# TSOC_GROVEY_FOUR.net
KiCad netlist of a schematic drawn in EAGLE
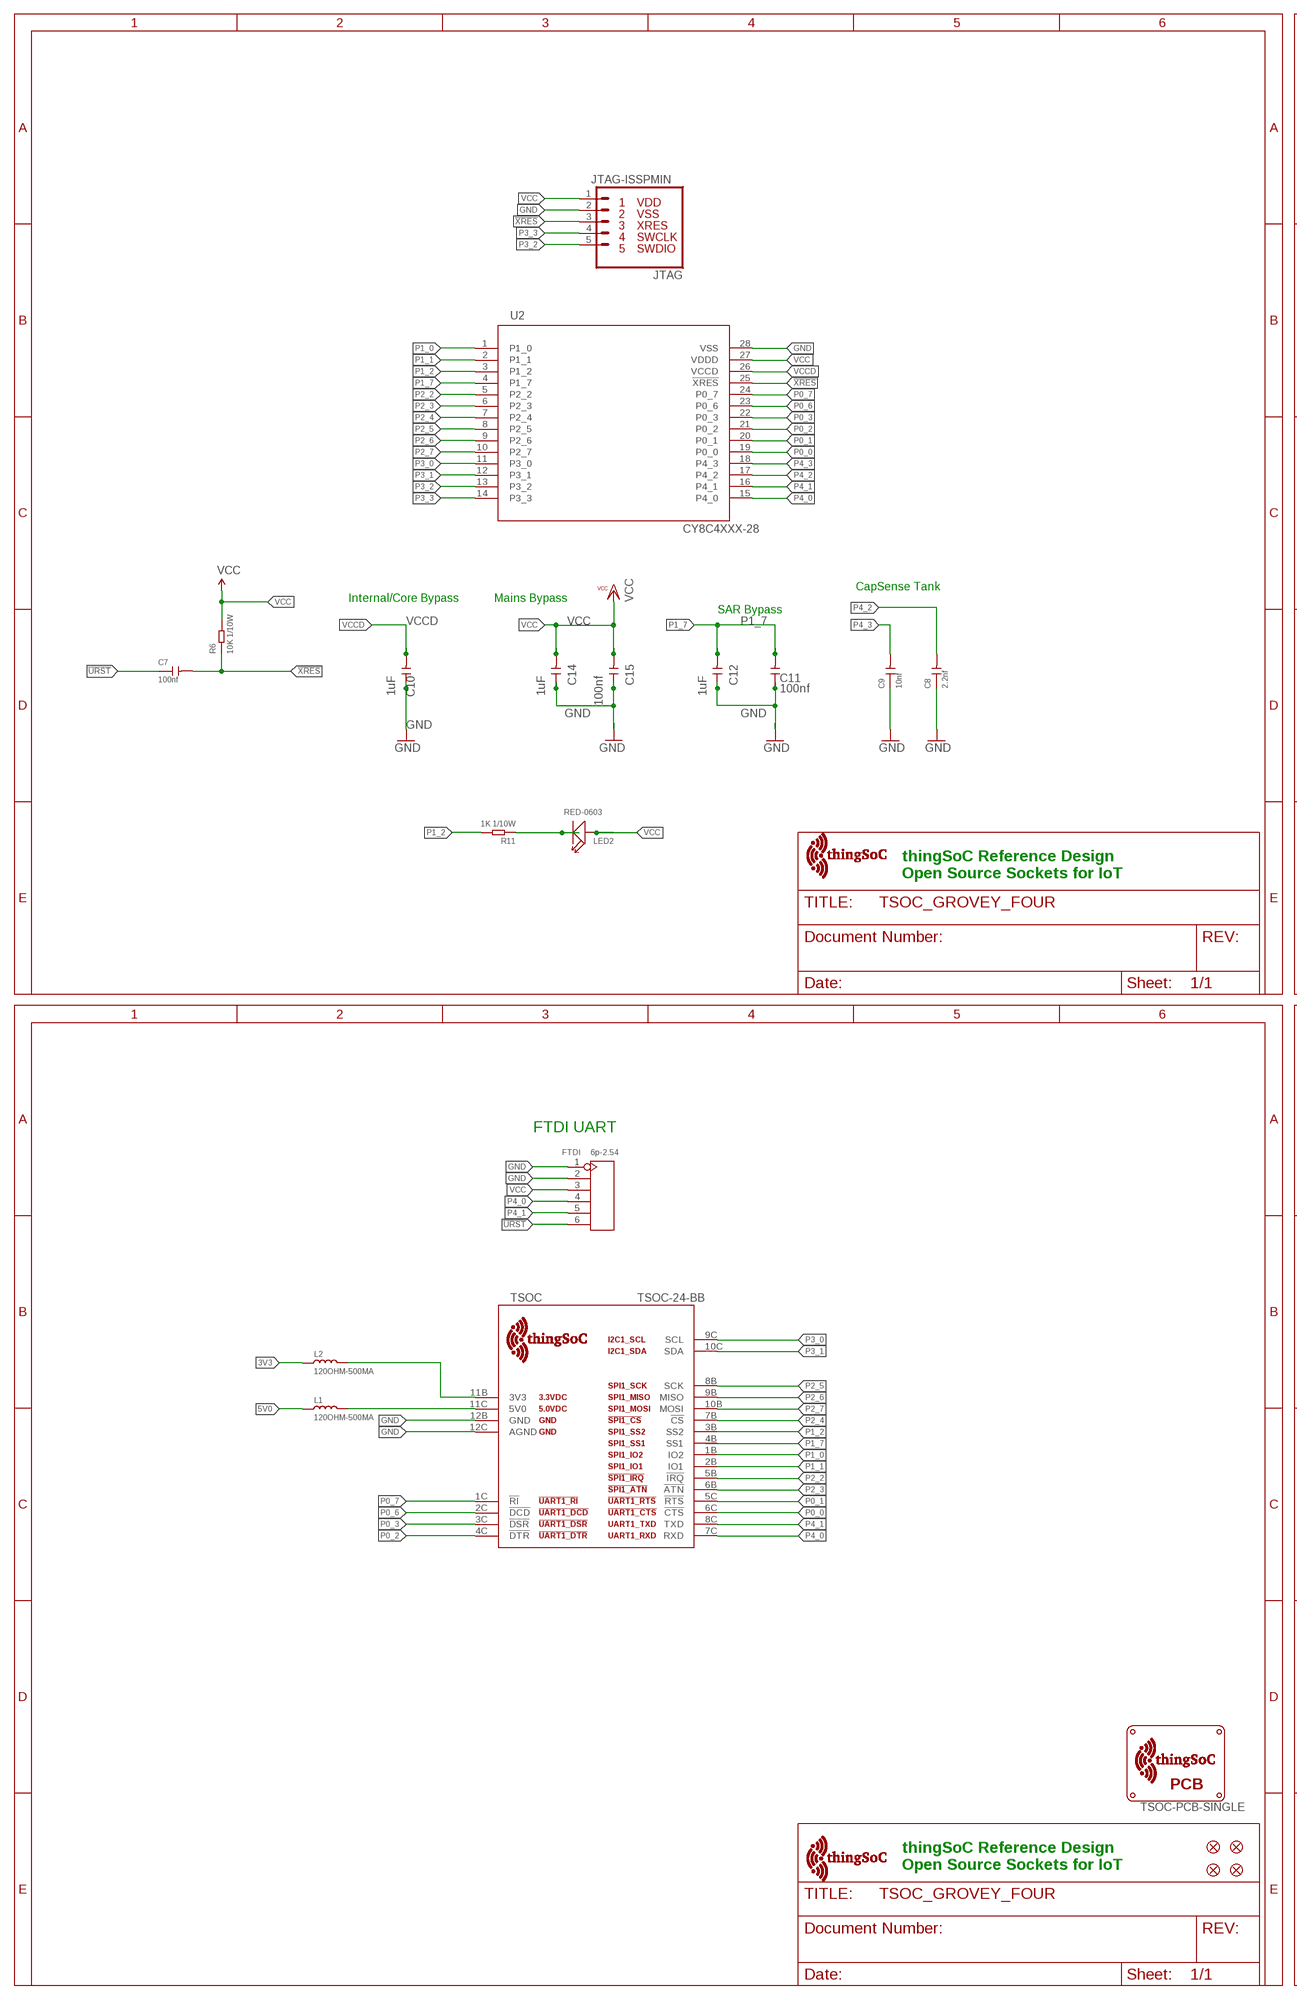
[diagram p0: schematic, sheet 1, part 1 of 2]
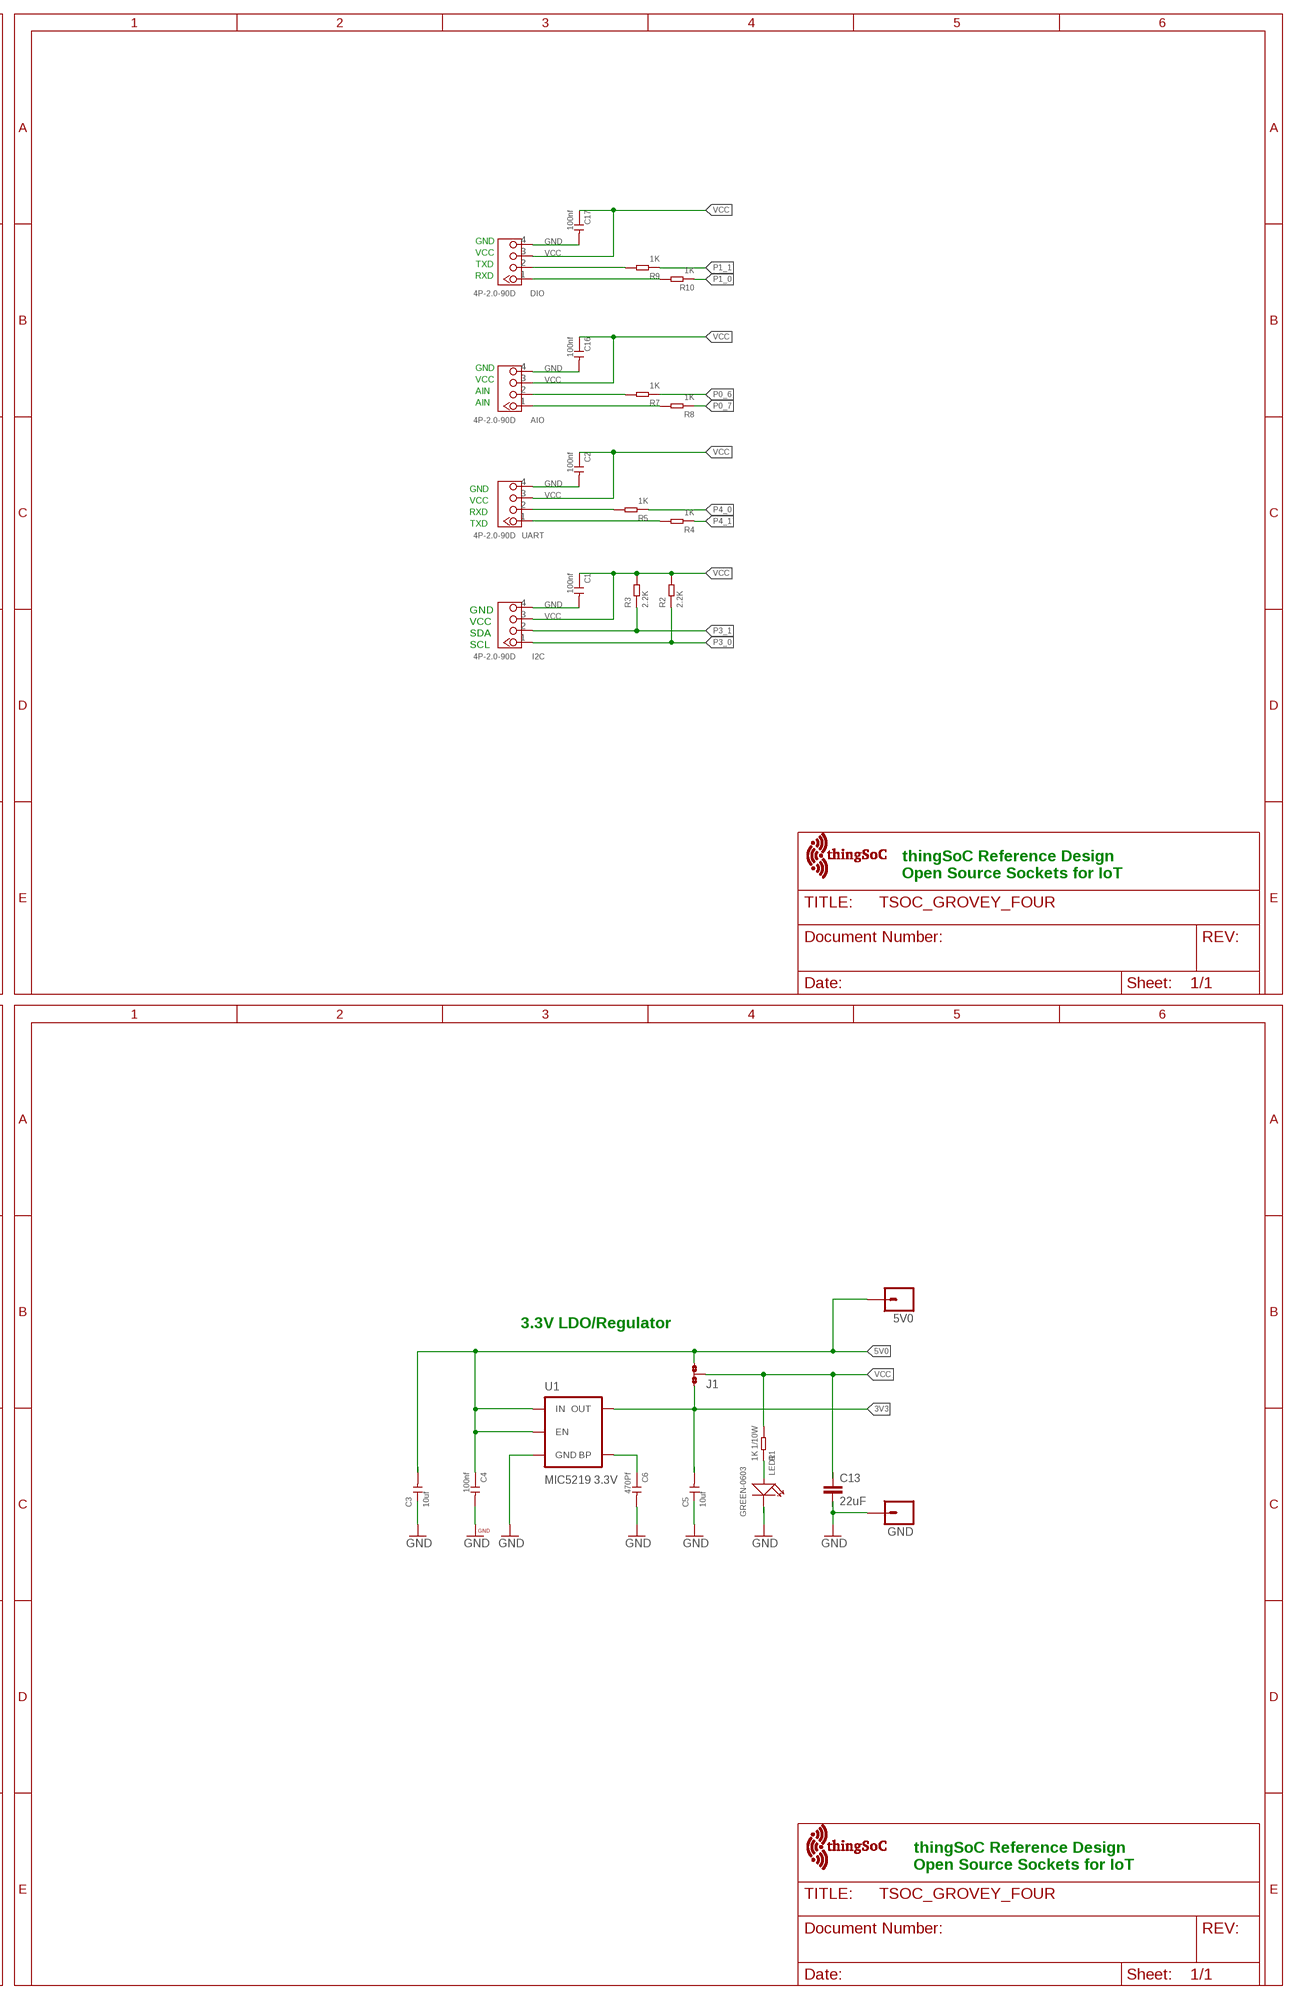
[diagram p1: schematic, sheet 1, part 2 of 2]

(export (version "E")
  (design (tool "Eeschema 10.0.6"))
  (components
    (comp (ref "$$U$1")
      (value "TSOC-PCB-SINGLE")
      (footprint "eagle-import:TSOC-BB-BRD-DIM")
      (libsource (lib "eagle-import") (part "TSOC-PCB-SINGLE"))
    )
    (comp (ref "5V0")
      (value "M01PTH")
      (footprint "eagle-import:1X01")
      (libsource (lib "eagle-import") (part "M01PTH"))
    )
    (comp (ref "AIO")
      (value "4P-2.0-90D")
      (footprint "eagle-import:HW4-2.0-90D")
      (libsource (lib "eagle-import") (part "GROVE-CONNECTOR-DIP-90D(4P-2.0)"))
    )
    (comp (ref "C1")
      (value "100nf")
      (footprint "eagle-import:C0603")
      (fields (field (name "MPN") "CC0603KRX7R9BB104"))
      (libsource (lib "eagle-import") (part "CERAMIC-100NF-50V-10%-X7R(0603)"))
    )
    (comp (ref "C2")
      (value "100nf")
      (footprint "eagle-import:C0603")
      (fields (field (name "MPN") "CC0603KRX7R9BB104"))
      (libsource (lib "eagle-import") (part "CERAMIC-100NF-50V-10%-X7R(0603)"))
    )
    (comp (ref "C3")
      (value "10uf")
      (footprint "eagle-import:C0603")
      (fields (field (name "MPN") "CC0603KRX5R6BB106"))
      (libsource (lib "eagle-import") (part "CERAMIC-10UF-10V-10%-X5R(0603)"))
    )
    (comp (ref "C4")
      (value "100nf")
      (footprint "eagle-import:C0603")
      (fields (field (name "MPN") "CC0603KRX7R9BB104"))
      (libsource (lib "eagle-import") (part "CERAMIC-100NF-50V-10%-X7R(0603)"))
    )
    (comp (ref "C5")
      (value "10uf")
      (footprint "eagle-import:C0603")
      (fields (field (name "MPN") "CC0603KRX5R6BB106"))
      (libsource (lib "eagle-import") (part "CERAMIC-10UF-10V-10%-X5R(0603)"))
    )
    (comp (ref "C6")
      (value "470Pf")
      (footprint "eagle-import:C0603")
      (fields (field (name "MPN") "CC0603KRX7R9BB104"))
      (libsource (lib "eagle-import") (part "CERAMIC-100NF-50V-10%-X7R(0603)"))
    )
    (comp (ref "C7")
      (value "100nf")
      (footprint "eagle-import:C0603")
      (fields (field (name "MPN") "CC0603KRX7R9BB104"))
      (libsource (lib "eagle-import") (part "CERAMIC-100NF-50V-10%-X7R(0603)"))
    )
    (comp (ref "C8")
      (value "2.2nf")
      (footprint "eagle-import:C0603")
      (fields (field (name "MPN") "GRM1885C1H102JA01D"))
      (libsource (lib "eagle-import") (part "CERAMIC-1NF-50V-5%-C0G(0603)"))
    )
    (comp (ref "C9")
      (value "10nf")
      (footprint "eagle-import:C0603")
      (fields (field (name "MPN") "CC0603KRX7R9BB103"))
      (libsource (lib "eagle-import") (part "CERAMIC-10NF-50V-10%-X7R(0603)"))
    )
    (comp (ref "C10")
      (value "1uF")
      (footprint "eagle-import:C0603")
      (fields (field (name "MPN") "CC0603KRX7R9BB104"))
      (libsource (lib "eagle-import") (part "CERAMIC-100NF-50V-10%-X7R(0603)"))
    )
    (comp (ref "C11")
      (value "100nf")
      (footprint "eagle-import:C0603")
      (fields (field (name "MPN") "CC0603KRX7R9BB104"))
      (libsource (lib "eagle-import") (part "CERAMIC-100NF-50V-10%-X7R(0603)"))
    )
    (comp (ref "C12")
      (value "1uF")
      (footprint "eagle-import:C0603")
      (fields (field (name "MPN") "CC0603KRX7R9BB104"))
      (libsource (lib "eagle-import") (part "CERAMIC-100NF-50V-10%-X7R(0603)"))
    )
    (comp (ref "C13")
      (value "22uF")
      (footprint "eagle-import:EIA-1206")
      (libsource (lib "eagle-import") (part "CAP-1206"))
    )
    (comp (ref "C14")
      (value "1uF")
      (footprint "eagle-import:C0603")
      (fields (field (name "MPN") "CC0603KRX7R9BB104"))
      (libsource (lib "eagle-import") (part "CERAMIC-100NF-50V-10%-X7R(0603)"))
    )
    (comp (ref "C15")
      (value "100nf")
      (footprint "eagle-import:C0603")
      (fields (field (name "MPN") "CC0603KRX7R9BB104"))
      (libsource (lib "eagle-import") (part "CERAMIC-100NF-50V-10%-X7R(0603)"))
    )
    (comp (ref "C16")
      (value "100nf")
      (footprint "eagle-import:C0603")
      (fields (field (name "MPN") "CC0603KRX7R9BB104"))
      (libsource (lib "eagle-import") (part "CERAMIC-100NF-50V-10%-X7R(0603)"))
    )
    (comp (ref "C17")
      (value "100nf")
      (footprint "eagle-import:C0603")
      (fields (field (name "MPN") "CC0603KRX7R9BB104"))
      (libsource (lib "eagle-import") (part "CERAMIC-100NF-50V-10%-X7R(0603)"))
    )
    (comp (ref "DIO")
      (value "4P-2.0-90D")
      (footprint "eagle-import:HW4-2.0-90D")
      (libsource (lib "eagle-import") (part "GROVE-CONNECTOR-DIP-90D(4P-2.0)"))
    )
    (comp (ref "FID1")
      (value "FIDUCIALUFIDUCIAL")
      (footprint "eagle-import:MICRO-FIDUCIAL")
      (libsource (lib "eagle-import") (part "FIDUCIALUFIDUCIAL"))
    )
    (comp (ref "FID2")
      (value "FIDUCIALUFIDUCIAL")
      (footprint "eagle-import:MICRO-FIDUCIAL")
      (libsource (lib "eagle-import") (part "FIDUCIALUFIDUCIAL"))
    )
    (comp (ref "FID3")
      (value "FIDUCIALUFIDUCIAL")
      (footprint "eagle-import:MICRO-FIDUCIAL")
      (libsource (lib "eagle-import") (part "FIDUCIALUFIDUCIAL"))
    )
    (comp (ref "FID4")
      (value "FIDUCIALUFIDUCIAL")
      (footprint "eagle-import:MICRO-FIDUCIAL")
      (libsource (lib "eagle-import") (part "FIDUCIALUFIDUCIAL"))
    )
    (comp (ref "FTDI")
      (value "6p-2.54")
      (footprint "eagle-import:H6-2.54")
      (fields (field (name "MPN") "P125-1106A1BS116A1"))
      (libsource (lib "eagle-import") (part "DIP-BLACK-MALE-HEADER(6P-2.54)"))
    )
    (comp (ref "GND")
      (value "M01PTH")
      (footprint "eagle-import:1X01")
      (libsource (lib "eagle-import") (part "M01PTH"))
    )
    (comp (ref "I2C")
      (value "4P-2.0-90D")
      (footprint "eagle-import:HW4-2.0-90D")
      (libsource (lib "eagle-import") (part "GROVE-CONNECTOR-DIP-90D(4P-2.0)"))
    )
    (comp (ref "J1")
      (value "NO")
      (footprint "eagle-import:JMP-3-NO-PTH-2.54")
      (libsource (lib "eagle-import") (part "JMP-3-NO-PTH"))
    )
    (comp (ref "JTAG")
      (value "JTAG-ISSPMIN")
      (footprint "eagle-import:PSOC_JTAG_MINSILK")
      (libsource (lib "eagle-import") (part "JTAG-ISSPMIN"))
    )
    (comp (ref "L1")
      (value "120OHM-500MA")
      (footprint "eagle-import:L0603")
      (fields (field (name "MPN") "BLM18AG121SN1D"))
      (libsource (lib "eagle-import") (part "SMD-FERRITE-CHIP-120-OHM-500MA(0603)"))
    )
    (comp (ref "L2")
      (value "120OHM-500MA")
      (footprint "eagle-import:L0603")
      (fields (field (name "MPN") "BLM18AG121SN1D"))
      (libsource (lib "eagle-import") (part "SMD-FERRITE-CHIP-120-OHM-500MA(0603)"))
    )
    (comp (ref "LED1")
      (value "GREEN-0603")
      (footprint "eagle-import:LED-0603")
      (fields (field (name "MPN") "19-217-G7C-AN1P2-3T"))
      (libsource (lib "eagle-import") (part "SMD-LED-CLEAR-GREEN(0603)"))
    )
    (comp (ref "LED2")
      (value "RED-0603")
      (footprint "eagle-import:LED-0603")
      (fields (field (name "MPN") "19-217-G7C-AN1P2-3T"))
      (libsource (lib "eagle-import") (part "SMD-LED-CLEAR-GREEN(0603)"))
    )
    (comp (ref "R1")
      (value "1K 1/10W")
      (footprint "eagle-import:R0603")
      (fields (field (name "MPN") "RC0603JR-071KL"))
      (libsource (lib "eagle-import") (part "SMD-RES-1K-5%-1/10W(0603)"))
    )
    (comp (ref "R2")
      (value "2.2K")
      (footprint "eagle-import:R0603")
      (fields (field (name "MPN") "RC0603JR-072K2L"))
      (libsource (lib "eagle-import") (part "SMD-RES-2.2K-5%-1/10W(0603)"))
    )
    (comp (ref "R3")
      (value "2.2K")
      (footprint "eagle-import:R0603")
      (fields (field (name "MPN") "RC0603JR-072K2L"))
      (libsource (lib "eagle-import") (part "SMD-RES-2.2K-5%-1/10W(0603)"))
    )
    (comp (ref "R4")
      (value "1K")
      (footprint "eagle-import:R0603")
      (fields (field (name "MPN") "RC0603JR-072K2L"))
      (libsource (lib "eagle-import") (part "SMD-RES-2.2K-5%-1/10W(0603)"))
    )
    (comp (ref "R5")
      (value "1K")
      (footprint "eagle-import:R0603")
      (fields (field (name "MPN") "RC0603JR-072K2L"))
      (libsource (lib "eagle-import") (part "SMD-RES-2.2K-5%-1/10W(0603)"))
    )
    (comp (ref "R6")
      (value "10K 1/10W")
      (footprint "eagle-import:R0603")
      (fields (field (name "MPN") "RC0603JR-0710KL"))
      (libsource (lib "eagle-import") (part "SMD-RES-10K-5%-1/10W(0603)"))
    )
    (comp (ref "R7")
      (value "1K")
      (footprint "eagle-import:R0603")
      (fields (field (name "MPN") "RC0603JR-072K2L"))
      (libsource (lib "eagle-import") (part "SMD-RES-2.2K-5%-1/10W(0603)"))
    )
    (comp (ref "R8")
      (value "1K")
      (footprint "eagle-import:R0603")
      (fields (field (name "MPN") "RC0603JR-072K2L"))
      (libsource (lib "eagle-import") (part "SMD-RES-2.2K-5%-1/10W(0603)"))
    )
    (comp (ref "R9")
      (value "1K")
      (footprint "eagle-import:R0603")
      (fields (field (name "MPN") "RC0603JR-072K2L"))
      (libsource (lib "eagle-import") (part "SMD-RES-2.2K-5%-1/10W(0603)"))
    )
    (comp (ref "R10")
      (value "1K")
      (footprint "eagle-import:R0603")
      (fields (field (name "MPN") "RC0603JR-072K2L"))
      (libsource (lib "eagle-import") (part "SMD-RES-2.2K-5%-1/10W(0603)"))
    )
    (comp (ref "R11")
      (value "1K 1/10W")
      (footprint "eagle-import:R0603")
      (fields (field (name "MPN") "RC0603JR-071KL"))
      (libsource (lib "eagle-import") (part "SMD-RES-1K-5%-1/10W(0603)"))
    )
    (comp (ref "TSOC")
      (value "TSOC-24-BB")
      (footprint "eagle-import:TSOC-BB-S24")
      (libsource (lib "eagle-import") (part "TSOC-24-BB"))
    )
    (comp (ref "U$1")
      (value "TSOC-LOGO-SMALL")
      (footprint "eagle-import:TSOC-LOGO-SML")
      (libsource (lib "eagle-import") (part "TSOC-LOGO-SMALL"))
    )
    (comp (ref "U$4")
      (value "TSOC-LOGO")
      (footprint "eagle-import:TSOC-LOGO-BLANK")
      (libsource (lib "eagle-import") (part "TSOC-LOGO"))
    )
    (comp (ref "U$102")
      (value "TSOC-LOGO-LRG")
      (footprint "eagle-import:TSOC-LOGO-LRG")
      (libsource (lib "eagle-import") (part "TSOC-LOGO-LRG"))
    )
    (comp (ref "U$103")
      (value "TSOC-LOGO-SMALL")
      (footprint "eagle-import:TSOC-LOGO-SML")
      (libsource (lib "eagle-import") (part "TSOC-LOGO-SMALL"))
    )
    (comp (ref "U1")
      (value "MIC5219 3.3V")
      (footprint "eagle-import:SOT23-5")
      (libsource (lib "eagle-import") (part "V_REG_MIC52193.3V"))
    )
    (comp (ref "U2")
      (value "CY8C4XXX-28")
      (footprint "eagle-import:SSOP28")
      (libsource (lib "eagle-import") (part "CY8C4XXX-28"))
    )
    (comp (ref "UART")
      (value "4P-2.0-90D")
      (footprint "eagle-import:HW4-2.0-90D")
      (libsource (lib "eagle-import") (part "GROVE-CONNECTOR-DIP-90D(4P-2.0)"))
    )
  )
  (nets
    (net (code "1") (name "/~{URST}") (class "Default")
      (node (ref "C7") (pin "1") (pinfunction "1_1") (pintype "passive"))
      (node (ref "FTDI") (pin "6") (pinfunction "6_6") (pintype "bidirectional"))
    )
    (net (code "2") (name "/~{XRES}") (class "Default")
      (node (ref "C7") (pin "2") (pinfunction "2_2") (pintype "passive"))
      (node (ref "JTAG") (pin "3") (pinfunction "3_3") (pintype "passive"))
      (node (ref "R6") (pin "1") (pinfunction "1_1") (pintype "passive"))
      (node (ref "U2") (pin "25") (pinfunction "~{XRES}_25") (pintype "bidirectional"))
    )
    (net (code "3") (name "3V3") (class "Default")
      (node (ref "C5") (pin "2") (pinfunction "2_2") (pintype "passive"))
      (node (ref "J1") (pin "1") (pinfunction "1_1") (pintype "passive"))
      (node (ref "L2") (pin "1") (pinfunction "1_1") (pintype "passive"))
      (node (ref "U1") (pin "5") (pinfunction "OUT_5") (pintype "passive"))
    )
    (net (code "4") (name "5V0") (class "Default")
      (node (ref "5V0") (pin "1") (pinfunction "1_1") (pintype "passive"))
      (node (ref "C3") (pin "2") (pinfunction "2_2") (pintype "passive"))
      (node (ref "C4") (pin "1") (pinfunction "1_1") (pintype "passive"))
      (node (ref "J1") (pin "3") (pinfunction "3_3") (pintype "passive"))
      (node (ref "L1") (pin "1") (pinfunction "1_1") (pintype "passive"))
      (node (ref "U1") (pin "1") (pinfunction "IN_1") (pintype "input"))
      (node (ref "U1") (pin "3") (pinfunction "EN_3") (pintype "input"))
    )
    (net (code "5") (name "GND") (class "Default")
      (node (ref "AIO") (pin "4") (pinfunction "4_4") (pintype "bidirectional"))
      (node (ref "C1") (pin "2") (pinfunction "2_2") (pintype "passive"))
      (node (ref "C10") (pin "1") (pinfunction "1_1") (pintype "passive"))
      (node (ref "C11") (pin "1") (pinfunction "1_1") (pintype "passive"))
      (node (ref "C12") (pin "1") (pinfunction "1_1") (pintype "passive"))
      (node (ref "C13") (pin "2") (pinfunction "2_2") (pintype "passive"))
      (node (ref "C14") (pin "1") (pinfunction "1_1") (pintype "passive"))
      (node (ref "C15") (pin "1") (pinfunction "1_1") (pintype "passive"))
      (node (ref "C16") (pin "2") (pinfunction "2_2") (pintype "passive"))
      (node (ref "C17") (pin "2") (pinfunction "2_2") (pintype "passive"))
      (node (ref "C2") (pin "2") (pinfunction "2_2") (pintype "passive"))
      (node (ref "C3") (pin "1") (pinfunction "1_1") (pintype "passive"))
      (node (ref "C4") (pin "2") (pinfunction "2_2") (pintype "passive"))
      (node (ref "C5") (pin "1") (pinfunction "1_1") (pintype "passive"))
      (node (ref "C6") (pin "2") (pinfunction "2_2") (pintype "passive"))
      (node (ref "C8") (pin "1") (pinfunction "1_1") (pintype "passive"))
      (node (ref "C9") (pin "1") (pinfunction "1_1") (pintype "passive"))
      (node (ref "DIO") (pin "4") (pinfunction "4_4") (pintype "bidirectional"))
      (node (ref "FTDI") (pin "1") (pinfunction "1_1") (pintype "bidirectional"))
      (node (ref "FTDI") (pin "2") (pinfunction "2_2") (pintype "bidirectional"))
      (node (ref "GND") (pin "1") (pinfunction "1_1") (pintype "passive"))
      (node (ref "I2C") (pin "4") (pinfunction "4_4") (pintype "bidirectional"))
      (node (ref "JTAG") (pin "2") (pinfunction "2_2") (pintype "passive"))
      (node (ref "LED1") (pin "-") (pinfunction "-_-") (pintype "passive"))
      (node (ref "TSOC") (pin "12B") (pinfunction "GND_12B") (pintype "bidirectional"))
      (node (ref "TSOC") (pin "12C") (pinfunction "AGND_12C") (pintype "bidirectional"))
      (node (ref "U1") (pin "2") (pinfunction "GND_2") (pintype "input"))
      (node (ref "U2") (pin "28") (pinfunction "VSS_28") (pintype "bidirectional"))
      (node (ref "UART") (pin "4") (pinfunction "4_4") (pintype "bidirectional"))
    )
    (net (code "6") (name "Net-(AIO-Pad1)") (class "Default")
      (node (ref "AIO") (pin "1") (pinfunction "1_1") (pintype "bidirectional"))
      (node (ref "R8") (pin "2") (pinfunction "2_2") (pintype "passive"))
    )
    (net (code "7") (name "Net-(AIO-Pad2)") (class "Default")
      (node (ref "AIO") (pin "2") (pinfunction "2_2") (pintype "bidirectional"))
      (node (ref "R7") (pin "2") (pinfunction "2_2") (pintype "passive"))
    )
    (net (code "8") (name "Net-(DIO-Pad1)") (class "Default")
      (node (ref "DIO") (pin "1") (pinfunction "1_1") (pintype "bidirectional"))
      (node (ref "R10") (pin "2") (pinfunction "2_2") (pintype "passive"))
    )
    (net (code "9") (name "Net-(DIO-Pad2)") (class "Default")
      (node (ref "DIO") (pin "2") (pinfunction "2_2") (pintype "bidirectional"))
      (node (ref "R9") (pin "2") (pinfunction "2_2") (pintype "passive"))
    )
    (net (code "10") (name "Net-(LED1-Pad+)") (class "Default")
      (node (ref "LED1") (pin "+") (pinfunction "+_+") (pintype "passive"))
      (node (ref "R1") (pin "1") (pinfunction "1_1") (pintype "passive"))
    )
    (net (code "11") (name "Net-(LED2-Pad-)") (class "Default")
      (node (ref "LED2") (pin "-") (pinfunction "-_-") (pintype "passive"))
      (node (ref "R11") (pin "1") (pinfunction "1_1") (pintype "passive"))
    )
    (net (code "12") (name "Net-(R4-Pad2)") (class "Default")
      (node (ref "R4") (pin "2") (pinfunction "2_2") (pintype "passive"))
      (node (ref "UART") (pin "1") (pinfunction "1_1") (pintype "bidirectional"))
    )
    (net (code "13") (name "Net-(R5-Pad2)") (class "Default")
      (node (ref "R5") (pin "2") (pinfunction "2_2") (pintype "passive"))
      (node (ref "UART") (pin "2") (pinfunction "2_2") (pintype "bidirectional"))
    )
    (net (code "14") (name "Net-(TSOC-3V3)") (class "Default")
      (node (ref "L2") (pin "2") (pinfunction "2_2") (pintype "passive"))
      (node (ref "TSOC") (pin "11B") (pinfunction "3V3_11B") (pintype "bidirectional"))
    )
    (net (code "15") (name "Net-(TSOC-5V0)") (class "Default")
      (node (ref "L1") (pin "2") (pinfunction "2_2") (pintype "passive"))
      (node (ref "TSOC") (pin "11C") (pinfunction "5V0_11C") (pintype "bidirectional"))
    )
    (net (code "16") (name "Net-(U1-BP)") (class "Default")
      (node (ref "C6") (pin "1") (pinfunction "1_1") (pintype "passive"))
      (node (ref "U1") (pin "4") (pinfunction "BP_4") (pintype "input"))
    )
    (net (code "17") (name "P0_0") (class "Default")
      (node (ref "TSOC") (pin "6C") (pinfunction "~{CTS}_6C") (pintype "bidirectional"))
      (node (ref "U2") (pin "19") (pinfunction "P0_0_19") (pintype "bidirectional"))
    )
    (net (code "18") (name "P0_1") (class "Default")
      (node (ref "TSOC") (pin "5C") (pinfunction "~{RTS}_5C") (pintype "bidirectional"))
      (node (ref "U2") (pin "20") (pinfunction "P0_1_20") (pintype "bidirectional"))
    )
    (net (code "19") (name "P0_2") (class "Default")
      (node (ref "TSOC") (pin "4C") (pinfunction "~{DTR}_4C") (pintype "bidirectional"))
      (node (ref "U2") (pin "21") (pinfunction "P0_2_21") (pintype "bidirectional"))
    )
    (net (code "20") (name "P0_3") (class "Default")
      (node (ref "TSOC") (pin "3C") (pinfunction "~{DSR}_3C") (pintype "bidirectional"))
      (node (ref "U2") (pin "22") (pinfunction "P0_3_22") (pintype "bidirectional"))
    )
    (net (code "21") (name "P0_6") (class "Default")
      (node (ref "R7") (pin "1") (pinfunction "1_1") (pintype "passive"))
      (node (ref "TSOC") (pin "2C") (pinfunction "~{DCD}_2C") (pintype "bidirectional"))
      (node (ref "U2") (pin "23") (pinfunction "P0_6_23") (pintype "bidirectional"))
    )
    (net (code "22") (name "P0_7") (class "Default")
      (node (ref "R8") (pin "1") (pinfunction "1_1") (pintype "passive"))
      (node (ref "TSOC") (pin "1C") (pinfunction "~{RI}_1C") (pintype "bidirectional"))
      (node (ref "U2") (pin "24") (pinfunction "P0_7_24") (pintype "bidirectional"))
    )
    (net (code "23") (name "P1_0") (class "Default")
      (node (ref "R10") (pin "1") (pinfunction "1_1") (pintype "passive"))
      (node (ref "TSOC") (pin "1B") (pinfunction "IO2_1B") (pintype "bidirectional"))
      (node (ref "U2") (pin "1") (pinfunction "P1_0_1") (pintype "bidirectional"))
    )
    (net (code "24") (name "P1_1") (class "Default")
      (node (ref "R9") (pin "1") (pinfunction "1_1") (pintype "passive"))
      (node (ref "TSOC") (pin "2B") (pinfunction "IO1_2B") (pintype "bidirectional"))
      (node (ref "U2") (pin "2") (pinfunction "P1_1_2") (pintype "bidirectional"))
    )
    (net (code "25") (name "P1_2") (class "Default")
      (node (ref "R11") (pin "2") (pinfunction "2_2") (pintype "passive"))
      (node (ref "TSOC") (pin "3B") (pinfunction "SS2_3B") (pintype "bidirectional"))
      (node (ref "U2") (pin "3") (pinfunction "P1_2_3") (pintype "bidirectional"))
    )
    (net (code "26") (name "P1_7") (class "Default")
      (node (ref "C11") (pin "2") (pinfunction "2_2") (pintype "passive"))
      (node (ref "C12") (pin "2") (pinfunction "2_2") (pintype "passive"))
      (node (ref "TSOC") (pin "4B") (pinfunction "SS1_4B") (pintype "bidirectional"))
      (node (ref "U2") (pin "4") (pinfunction "P1_7_4") (pintype "bidirectional"))
    )
    (net (code "27") (name "P2_2") (class "Default")
      (node (ref "TSOC") (pin "5B") (pinfunction "~{IRQ}_5B") (pintype "bidirectional"))
      (node (ref "U2") (pin "5") (pinfunction "P2_2_5") (pintype "bidirectional"))
    )
    (net (code "28") (name "P2_3") (class "Default")
      (node (ref "TSOC") (pin "6B") (pinfunction "~{ATN}_6B") (pintype "bidirectional"))
      (node (ref "U2") (pin "6") (pinfunction "P2_3_6") (pintype "bidirectional"))
    )
    (net (code "29") (name "P2_4") (class "Default")
      (node (ref "TSOC") (pin "7B") (pinfunction "~{CS}_7B") (pintype "bidirectional"))
      (node (ref "U2") (pin "7") (pinfunction "P2_4_7") (pintype "bidirectional"))
    )
    (net (code "30") (name "P2_5") (class "Default")
      (node (ref "TSOC") (pin "8B") (pinfunction "SCK_8B") (pintype "bidirectional"))
      (node (ref "U2") (pin "8") (pinfunction "P2_5_8") (pintype "bidirectional"))
    )
    (net (code "31") (name "P2_6") (class "Default")
      (node (ref "TSOC") (pin "9B") (pinfunction "MISO_9B") (pintype "bidirectional"))
      (node (ref "U2") (pin "9") (pinfunction "P2_6_9") (pintype "bidirectional"))
    )
    (net (code "32") (name "P2_7") (class "Default")
      (node (ref "TSOC") (pin "10B") (pinfunction "MOSI_10B") (pintype "bidirectional"))
      (node (ref "U2") (pin "10") (pinfunction "P2_7_10") (pintype "bidirectional"))
    )
    (net (code "33") (name "P3_0") (class "Default")
      (node (ref "I2C") (pin "1") (pinfunction "1_1") (pintype "bidirectional"))
      (node (ref "R2") (pin "1") (pinfunction "1_1") (pintype "passive"))
      (node (ref "TSOC") (pin "9C") (pinfunction "SCL_9C") (pintype "bidirectional"))
      (node (ref "U2") (pin "11") (pinfunction "P3_0_11") (pintype "bidirectional"))
    )
    (net (code "34") (name "P3_1") (class "Default")
      (node (ref "I2C") (pin "2") (pinfunction "2_2") (pintype "bidirectional"))
      (node (ref "R3") (pin "1") (pinfunction "1_1") (pintype "passive"))
      (node (ref "TSOC") (pin "10C") (pinfunction "SDA_10C") (pintype "bidirectional"))
      (node (ref "U2") (pin "12") (pinfunction "P3_1_12") (pintype "bidirectional"))
    )
    (net (code "35") (name "P3_2") (class "Default")
      (node (ref "JTAG") (pin "5") (pinfunction "5_5") (pintype "passive"))
      (node (ref "U2") (pin "13") (pinfunction "P3_2_13") (pintype "bidirectional"))
    )
    (net (code "36") (name "P3_3") (class "Default")
      (node (ref "JTAG") (pin "4") (pinfunction "4_4") (pintype "passive"))
      (node (ref "U2") (pin "14") (pinfunction "P3_3_14") (pintype "bidirectional"))
    )
    (net (code "37") (name "P4_0") (class "Default")
      (node (ref "FTDI") (pin "4") (pinfunction "4_4") (pintype "bidirectional"))
      (node (ref "R5") (pin "1") (pinfunction "1_1") (pintype "passive"))
      (node (ref "TSOC") (pin "7C") (pinfunction "RXD_7C") (pintype "bidirectional"))
      (node (ref "U2") (pin "15") (pinfunction "P4_0_15") (pintype "bidirectional"))
    )
    (net (code "38") (name "P4_1") (class "Default")
      (node (ref "FTDI") (pin "5") (pinfunction "5_5") (pintype "bidirectional"))
      (node (ref "R4") (pin "1") (pinfunction "1_1") (pintype "passive"))
      (node (ref "TSOC") (pin "8C") (pinfunction "TXD_8C") (pintype "bidirectional"))
      (node (ref "U2") (pin "16") (pinfunction "P4_1_16") (pintype "bidirectional"))
    )
    (net (code "39") (name "P4_2") (class "Default")
      (node (ref "C8") (pin "2") (pinfunction "2_2") (pintype "passive"))
      (node (ref "U2") (pin "17") (pinfunction "P4_2_17") (pintype "bidirectional"))
    )
    (net (code "40") (name "P4_3") (class "Default")
      (node (ref "C9") (pin "2") (pinfunction "2_2") (pintype "passive"))
      (node (ref "U2") (pin "18") (pinfunction "P4_3_18") (pintype "bidirectional"))
    )
    (net (code "41") (name "VCC") (class "Default")
      (node (ref "AIO") (pin "3") (pinfunction "3_3") (pintype "bidirectional"))
      (node (ref "C1") (pin "1") (pinfunction "1_1") (pintype "passive"))
      (node (ref "C13") (pin "1") (pinfunction "1_1") (pintype "passive"))
      (node (ref "C14") (pin "2") (pinfunction "2_2") (pintype "passive"))
      (node (ref "C15") (pin "2") (pinfunction "2_2") (pintype "passive"))
      (node (ref "C16") (pin "1") (pinfunction "1_1") (pintype "passive"))
      (node (ref "C17") (pin "1") (pinfunction "1_1") (pintype "passive"))
      (node (ref "C2") (pin "1") (pinfunction "1_1") (pintype "passive"))
      (node (ref "DIO") (pin "3") (pinfunction "3_3") (pintype "bidirectional"))
      (node (ref "FTDI") (pin "3") (pinfunction "3_3") (pintype "bidirectional"))
      (node (ref "I2C") (pin "3") (pinfunction "3_3") (pintype "bidirectional"))
      (node (ref "J1") (pin "2") (pinfunction "2_2") (pintype "passive"))
      (node (ref "JTAG") (pin "1") (pinfunction "1_1") (pintype "passive"))
      (node (ref "LED2") (pin "+") (pinfunction "+_+") (pintype "passive"))
      (node (ref "R1") (pin "2") (pinfunction "2_2") (pintype "passive"))
      (node (ref "R2") (pin "2") (pinfunction "2_2") (pintype "passive"))
      (node (ref "R3") (pin "2") (pinfunction "2_2") (pintype "passive"))
      (node (ref "R6") (pin "2") (pinfunction "2_2") (pintype "passive"))
      (node (ref "U2") (pin "27") (pinfunction "VDDD_27") (pintype "bidirectional"))
      (node (ref "UART") (pin "3") (pinfunction "3_3") (pintype "bidirectional"))
    )
    (net (code "42") (name "VCCD") (class "Default")
      (node (ref "C10") (pin "2") (pinfunction "2_2") (pintype "passive"))
      (node (ref "U2") (pin "26") (pinfunction "VCCD_26") (pintype "bidirectional"))
    )
  )
)
